# LED_2.net
KiCad netlist of a schematic drawn in Altium Designer
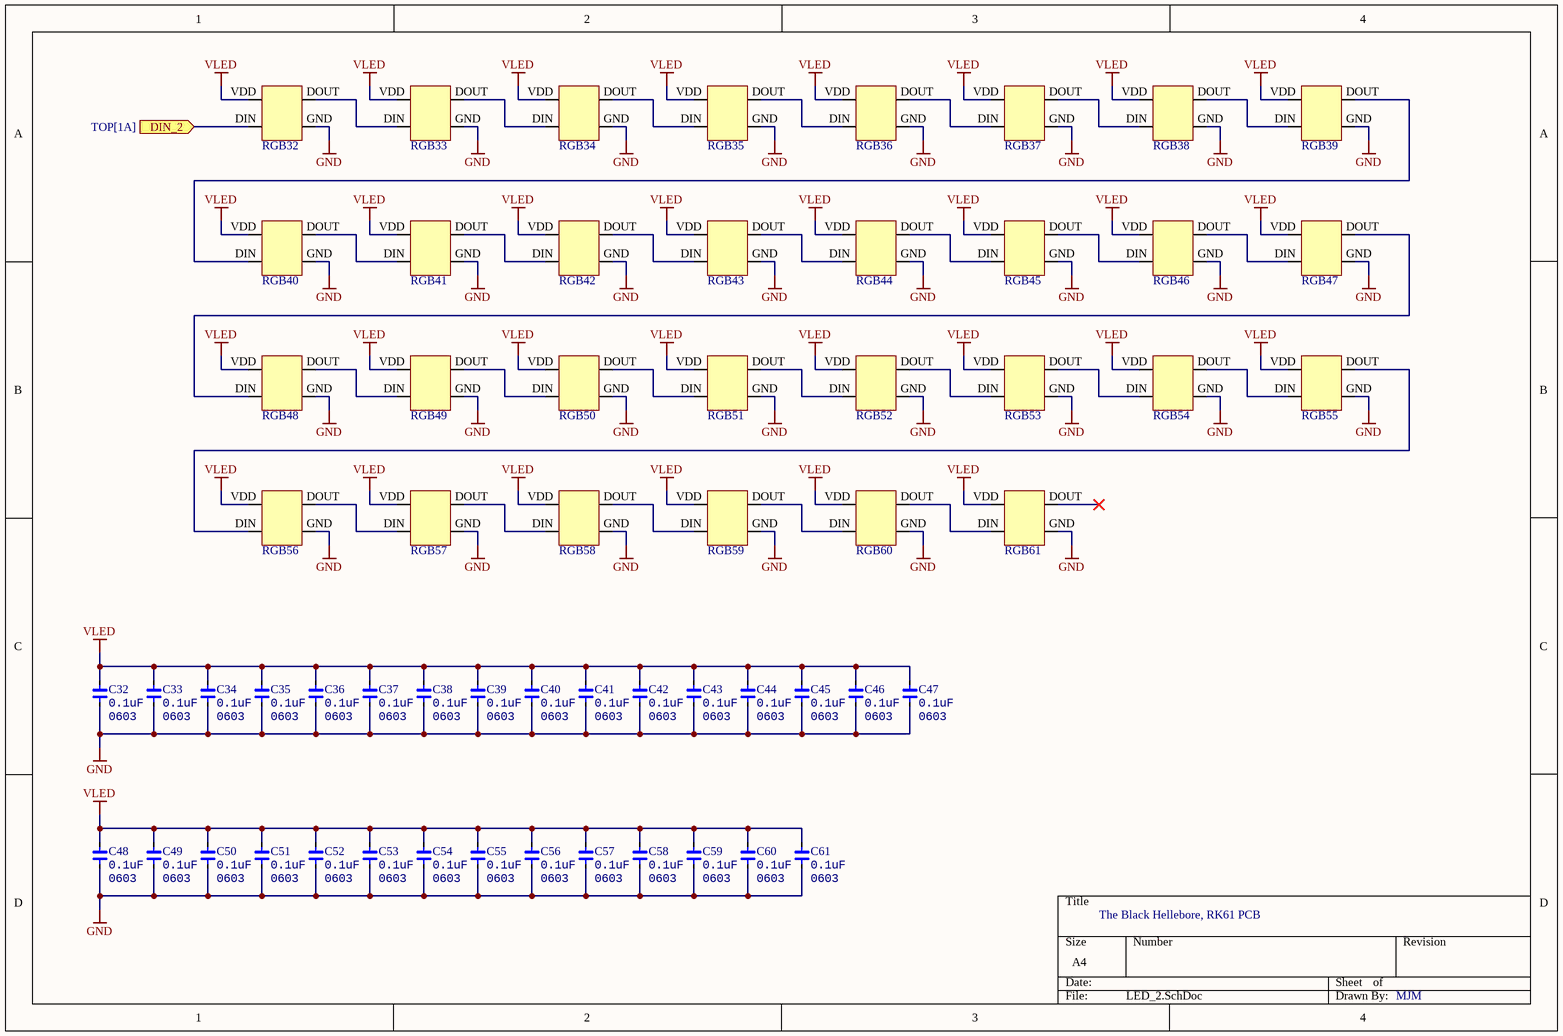
[diagram p0: LED_2.SchDoc]

(export (version "E")
  (design (tool "Eeschema 10.0.6"))
  (components
    (comp (ref "C32")
      (value "0.1uF")
      (footprint "FP-CC0603-DA-MFG")
      (description "0603 0.1 uF 50 V ±5 % Tolerance X7R SMT Multilayer Ceramic Capacitor")
      (fields (field (name "TYPE") "0603") (field (name "Comment") "CC0603JRX7R9BB104"))
      (libsource (lib "Microcom Corporation") (part "M_Cap"))
    )
    (comp (ref "C33")
      (value "0.1uF")
      (footprint "FP-CC0603-DA-MFG")
      (description "0603 0.1 uF 50 V ±5 % Tolerance X7R SMT Multilayer Ceramic Capacitor")
      (fields (field (name "TYPE") "0603") (field (name "Comment") "CC0603JRX7R9BB104"))
      (libsource (lib "Microcom Corporation") (part "M_Cap"))
    )
    (comp (ref "C34")
      (value "0.1uF")
      (footprint "FP-CC0603-DA-MFG")
      (description "0603 0.1 uF 50 V ±5 % Tolerance X7R SMT Multilayer Ceramic Capacitor")
      (fields (field (name "TYPE") "0603") (field (name "Comment") "CC0603JRX7R9BB104"))
      (libsource (lib "Microcom Corporation") (part "M_Cap"))
    )
    (comp (ref "C35")
      (value "0.1uF")
      (footprint "FP-CC0603-DA-MFG")
      (description "0603 0.1 uF 50 V ±5 % Tolerance X7R SMT Multilayer Ceramic Capacitor")
      (fields (field (name "TYPE") "0603") (field (name "Comment") "CC0603JRX7R9BB104"))
      (libsource (lib "Microcom Corporation") (part "M_Cap"))
    )
    (comp (ref "C36")
      (value "0.1uF")
      (footprint "FP-CC0603-DA-MFG")
      (description "0603 0.1 uF 50 V ±5 % Tolerance X7R SMT Multilayer Ceramic Capacitor")
      (fields (field (name "TYPE") "0603") (field (name "Comment") "CC0603JRX7R9BB104"))
      (libsource (lib "Microcom Corporation") (part "M_Cap"))
    )
    (comp (ref "C37")
      (value "0.1uF")
      (footprint "FP-CC0603-DA-MFG")
      (description "0603 0.1 uF 50 V ±5 % Tolerance X7R SMT Multilayer Ceramic Capacitor")
      (fields (field (name "TYPE") "0603") (field (name "Comment") "CC0603JRX7R9BB104"))
      (libsource (lib "Microcom Corporation") (part "M_Cap"))
    )
    (comp (ref "C38")
      (value "0.1uF")
      (footprint "FP-CC0603-DA-MFG")
      (description "0603 0.1 uF 50 V ±5 % Tolerance X7R SMT Multilayer Ceramic Capacitor")
      (fields (field (name "TYPE") "0603") (field (name "Comment") "CC0603JRX7R9BB104"))
      (libsource (lib "Microcom Corporation") (part "M_Cap"))
    )
    (comp (ref "C39")
      (value "0.1uF")
      (footprint "FP-CC0603-DA-MFG")
      (description "0603 0.1 uF 50 V ±5 % Tolerance X7R SMT Multilayer Ceramic Capacitor")
      (fields (field (name "TYPE") "0603") (field (name "Comment") "CC0603JRX7R9BB104"))
      (libsource (lib "Microcom Corporation") (part "M_Cap"))
    )
    (comp (ref "C40")
      (value "0.1uF")
      (footprint "FP-CC0603-DA-MFG")
      (description "0603 0.1 uF 50 V ±5 % Tolerance X7R SMT Multilayer Ceramic Capacitor")
      (fields (field (name "TYPE") "0603") (field (name "Comment") "CC0603JRX7R9BB104"))
      (libsource (lib "Microcom Corporation") (part "M_Cap"))
    )
    (comp (ref "C41")
      (value "0.1uF")
      (footprint "FP-CC0603-DA-MFG")
      (description "0603 0.1 uF 50 V ±5 % Tolerance X7R SMT Multilayer Ceramic Capacitor")
      (fields (field (name "TYPE") "0603") (field (name "Comment") "CC0603JRX7R9BB104"))
      (libsource (lib "Microcom Corporation") (part "M_Cap"))
    )
    (comp (ref "C42")
      (value "0.1uF")
      (footprint "FP-CC0603-DA-MFG")
      (description "0603 0.1 uF 50 V ±5 % Tolerance X7R SMT Multilayer Ceramic Capacitor")
      (fields (field (name "TYPE") "0603") (field (name "Comment") "CC0603JRX7R9BB104"))
      (libsource (lib "Microcom Corporation") (part "M_Cap"))
    )
    (comp (ref "C43")
      (value "0.1uF")
      (footprint "FP-CC0603-DA-MFG")
      (description "0603 0.1 uF 50 V ±5 % Tolerance X7R SMT Multilayer Ceramic Capacitor")
      (fields (field (name "TYPE") "0603") (field (name "Comment") "CC0603JRX7R9BB104"))
      (libsource (lib "Microcom Corporation") (part "M_Cap"))
    )
    (comp (ref "C44")
      (value "0.1uF")
      (footprint "FP-CC0603-DA-MFG")
      (description "0603 0.1 uF 50 V ±5 % Tolerance X7R SMT Multilayer Ceramic Capacitor")
      (fields (field (name "TYPE") "0603") (field (name "Comment") "CC0603JRX7R9BB104"))
      (libsource (lib "Microcom Corporation") (part "M_Cap"))
    )
    (comp (ref "C45")
      (value "0.1uF")
      (footprint "FP-CC0603-DA-MFG")
      (description "0603 0.1 uF 50 V ±5 % Tolerance X7R SMT Multilayer Ceramic Capacitor")
      (fields (field (name "TYPE") "0603") (field (name "Comment") "CC0603JRX7R9BB104"))
      (libsource (lib "Microcom Corporation") (part "M_Cap"))
    )
    (comp (ref "C46")
      (value "0.1uF")
      (footprint "FP-CC0603-DA-MFG")
      (description "0603 0.1 uF 50 V ±5 % Tolerance X7R SMT Multilayer Ceramic Capacitor")
      (fields (field (name "TYPE") "0603") (field (name "Comment") "CC0603JRX7R9BB104"))
      (libsource (lib "Microcom Corporation") (part "M_Cap"))
    )
    (comp (ref "C47")
      (value "0.1uF")
      (footprint "FP-CC0603-DA-MFG")
      (description "0603 0.1 uF 50 V ±5 % Tolerance X7R SMT Multilayer Ceramic Capacitor")
      (fields (field (name "TYPE") "0603") (field (name "Comment") "CC0603JRX7R9BB104"))
      (libsource (lib "Microcom Corporation") (part "M_Cap"))
    )
    (comp (ref "C48")
      (value "0.1uF")
      (footprint "FP-CC0603-DA-MFG")
      (description "0603 0.1 uF 50 V ±5 % Tolerance X7R SMT Multilayer Ceramic Capacitor")
      (fields (field (name "TYPE") "0603") (field (name "Comment") "CC0603JRX7R9BB104"))
      (libsource (lib "Microcom Corporation") (part "M_Cap"))
    )
    (comp (ref "C49")
      (value "0.1uF")
      (footprint "FP-CC0603-DA-MFG")
      (description "0603 0.1 uF 50 V ±5 % Tolerance X7R SMT Multilayer Ceramic Capacitor")
      (fields (field (name "TYPE") "0603") (field (name "Comment") "CC0603JRX7R9BB104"))
      (libsource (lib "Microcom Corporation") (part "M_Cap"))
    )
    (comp (ref "C50")
      (value "0.1uF")
      (footprint "FP-CC0603-DA-MFG")
      (description "0603 0.1 uF 50 V ±5 % Tolerance X7R SMT Multilayer Ceramic Capacitor")
      (fields (field (name "TYPE") "0603") (field (name "Comment") "CC0603JRX7R9BB104"))
      (libsource (lib "Microcom Corporation") (part "M_Cap"))
    )
    (comp (ref "C51")
      (value "0.1uF")
      (footprint "FP-CC0603-DA-MFG")
      (description "0603 0.1 uF 50 V ±5 % Tolerance X7R SMT Multilayer Ceramic Capacitor")
      (fields (field (name "TYPE") "0603") (field (name "Comment") "CC0603JRX7R9BB104"))
      (libsource (lib "Microcom Corporation") (part "M_Cap"))
    )
    (comp (ref "C52")
      (value "0.1uF")
      (footprint "FP-CC0603-DA-MFG")
      (description "0603 0.1 uF 50 V ±5 % Tolerance X7R SMT Multilayer Ceramic Capacitor")
      (fields (field (name "TYPE") "0603") (field (name "Comment") "CC0603JRX7R9BB104"))
      (libsource (lib "Microcom Corporation") (part "M_Cap"))
    )
    (comp (ref "C53")
      (value "0.1uF")
      (footprint "FP-CC0603-DA-MFG")
      (description "0603 0.1 uF 50 V ±5 % Tolerance X7R SMT Multilayer Ceramic Capacitor")
      (fields (field (name "TYPE") "0603") (field (name "Comment") "CC0603JRX7R9BB104"))
      (libsource (lib "Microcom Corporation") (part "M_Cap"))
    )
    (comp (ref "C54")
      (value "0.1uF")
      (footprint "FP-CC0603-DA-MFG")
      (description "0603 0.1 uF 50 V ±5 % Tolerance X7R SMT Multilayer Ceramic Capacitor")
      (fields (field (name "TYPE") "0603") (field (name "Comment") "CC0603JRX7R9BB104"))
      (libsource (lib "Microcom Corporation") (part "M_Cap"))
    )
    (comp (ref "C55")
      (value "0.1uF")
      (footprint "FP-CC0603-DA-MFG")
      (description "0603 0.1 uF 50 V ±5 % Tolerance X7R SMT Multilayer Ceramic Capacitor")
      (fields (field (name "TYPE") "0603") (field (name "Comment") "CC0603JRX7R9BB104"))
      (libsource (lib "Microcom Corporation") (part "M_Cap"))
    )
    (comp (ref "C56")
      (value "0.1uF")
      (footprint "FP-CC0603-DA-MFG")
      (description "0603 0.1 uF 50 V ±5 % Tolerance X7R SMT Multilayer Ceramic Capacitor")
      (fields (field (name "TYPE") "0603") (field (name "Comment") "CC0603JRX7R9BB104"))
      (libsource (lib "Microcom Corporation") (part "M_Cap"))
    )
    (comp (ref "C57")
      (value "0.1uF")
      (footprint "FP-CC0603-DA-MFG")
      (description "0603 0.1 uF 50 V ±5 % Tolerance X7R SMT Multilayer Ceramic Capacitor")
      (fields (field (name "TYPE") "0603") (field (name "Comment") "CC0603JRX7R9BB104"))
      (libsource (lib "Microcom Corporation") (part "M_Cap"))
    )
    (comp (ref "C58")
      (value "0.1uF")
      (footprint "FP-CC0603-DA-MFG")
      (description "0603 0.1 uF 50 V ±5 % Tolerance X7R SMT Multilayer Ceramic Capacitor")
      (fields (field (name "TYPE") "0603") (field (name "Comment") "CC0603JRX7R9BB104"))
      (libsource (lib "Microcom Corporation") (part "M_Cap"))
    )
    (comp (ref "C59")
      (value "0.1uF")
      (footprint "FP-CC0603-DA-MFG")
      (description "0603 0.1 uF 50 V ±5 % Tolerance X7R SMT Multilayer Ceramic Capacitor")
      (fields (field (name "TYPE") "0603") (field (name "Comment") "CC0603JRX7R9BB104"))
      (libsource (lib "Microcom Corporation") (part "M_Cap"))
    )
    (comp (ref "C60")
      (value "0.1uF")
      (footprint "FP-CC0603-DA-MFG")
      (description "0603 0.1 uF 50 V ±5 % Tolerance X7R SMT Multilayer Ceramic Capacitor")
      (fields (field (name "TYPE") "0603") (field (name "Comment") "CC0603JRX7R9BB104"))
      (libsource (lib "Microcom Corporation") (part "M_Cap"))
    )
    (comp (ref "C61")
      (value "0.1uF")
      (footprint "FP-CC0603-DA-MFG")
      (description "0603 0.1 uF 50 V ±5 % Tolerance X7R SMT Multilayer Ceramic Capacitor")
      (fields (field (name "TYPE") "0603") (field (name "Comment") "CC0603JRX7R9BB104"))
      (libsource (lib "Microcom Corporation") (part "M_Cap"))
    )
    (comp (ref "RGB32")
      (value "SK6812MINI-E")
      (footprint "sk6812minie")
      (description "RGB LED SK6812MINI-E")
      (libsource (lib "Microcom Corporation") (part "SK6812MINI-E"))
    )
    (comp (ref "RGB33")
      (value "SK6812MINI-E")
      (footprint "sk6812minie")
      (description "RGB LED SK6812MINI-E")
      (libsource (lib "Microcom Corporation") (part "SK6812MINI-E"))
    )
    (comp (ref "RGB34")
      (value "SK6812MINI-E")
      (footprint "sk6812minie")
      (description "RGB LED SK6812MINI-E")
      (libsource (lib "Microcom Corporation") (part "SK6812MINI-E"))
    )
    (comp (ref "RGB35")
      (value "SK6812MINI-E")
      (footprint "sk6812minie")
      (description "RGB LED SK6812MINI-E")
      (libsource (lib "Microcom Corporation") (part "SK6812MINI-E"))
    )
    (comp (ref "RGB36")
      (value "SK6812MINI-E")
      (footprint "sk6812minie")
      (description "RGB LED SK6812MINI-E")
      (libsource (lib "Microcom Corporation") (part "SK6812MINI-E"))
    )
    (comp (ref "RGB37")
      (value "SK6812MINI-E")
      (footprint "sk6812minie")
      (description "RGB LED SK6812MINI-E")
      (libsource (lib "Microcom Corporation") (part "SK6812MINI-E"))
    )
    (comp (ref "RGB38")
      (value "SK6812MINI-E")
      (footprint "sk6812minie")
      (description "RGB LED SK6812MINI-E")
      (libsource (lib "Microcom Corporation") (part "SK6812MINI-E"))
    )
    (comp (ref "RGB39")
      (value "SK6812MINI-E")
      (footprint "sk6812minie")
      (description "RGB LED SK6812MINI-E")
      (libsource (lib "Microcom Corporation") (part "SK6812MINI-E"))
    )
    (comp (ref "RGB40")
      (value "SK6812MINI-E")
      (footprint "sk6812minie")
      (description "RGB LED SK6812MINI-E")
      (libsource (lib "Microcom Corporation") (part "SK6812MINI-E"))
    )
    (comp (ref "RGB41")
      (value "SK6812MINI-E")
      (footprint "sk6812minie")
      (description "RGB LED SK6812MINI-E")
      (libsource (lib "Microcom Corporation") (part "SK6812MINI-E"))
    )
    (comp (ref "RGB42")
      (value "SK6812MINI-E")
      (footprint "sk6812minie")
      (description "RGB LED SK6812MINI-E")
      (libsource (lib "Microcom Corporation") (part "SK6812MINI-E"))
    )
    (comp (ref "RGB43")
      (value "SK6812MINI-E")
      (footprint "sk6812minie")
      (description "RGB LED SK6812MINI-E")
      (libsource (lib "Microcom Corporation") (part "SK6812MINI-E"))
    )
    (comp (ref "RGB44")
      (value "SK6812MINI-E")
      (footprint "sk6812minie")
      (description "RGB LED SK6812MINI-E")
      (libsource (lib "Microcom Corporation") (part "SK6812MINI-E"))
    )
    (comp (ref "RGB45")
      (value "SK6812MINI-E")
      (footprint "sk6812minie")
      (description "RGB LED SK6812MINI-E")
      (libsource (lib "Microcom Corporation") (part "SK6812MINI-E"))
    )
    (comp (ref "RGB46")
      (value "SK6812MINI-E")
      (footprint "sk6812minie")
      (description "RGB LED SK6812MINI-E")
      (libsource (lib "Microcom Corporation") (part "SK6812MINI-E"))
    )
    (comp (ref "RGB47")
      (value "SK6812MINI-E")
      (footprint "sk6812minie")
      (description "RGB LED SK6812MINI-E")
      (libsource (lib "Microcom Corporation") (part "SK6812MINI-E"))
    )
    (comp (ref "RGB48")
      (value "SK6812MINI-E")
      (footprint "sk6812minie")
      (description "RGB LED SK6812MINI-E")
      (libsource (lib "Microcom Corporation") (part "SK6812MINI-E"))
    )
    (comp (ref "RGB49")
      (value "SK6812MINI-E")
      (footprint "sk6812minie")
      (description "RGB LED SK6812MINI-E")
      (libsource (lib "Microcom Corporation") (part "SK6812MINI-E"))
    )
    (comp (ref "RGB50")
      (value "SK6812MINI-E")
      (footprint "sk6812minie")
      (description "RGB LED SK6812MINI-E")
      (libsource (lib "Microcom Corporation") (part "SK6812MINI-E"))
    )
    (comp (ref "RGB51")
      (value "SK6812MINI-E")
      (footprint "sk6812minie")
      (description "RGB LED SK6812MINI-E")
      (libsource (lib "Microcom Corporation") (part "SK6812MINI-E"))
    )
    (comp (ref "RGB52")
      (value "SK6812MINI-E")
      (footprint "sk6812minie")
      (description "RGB LED SK6812MINI-E")
      (libsource (lib "Microcom Corporation") (part "SK6812MINI-E"))
    )
    (comp (ref "RGB53")
      (value "SK6812MINI-E")
      (footprint "sk6812minie")
      (description "RGB LED SK6812MINI-E")
      (libsource (lib "Microcom Corporation") (part "SK6812MINI-E"))
    )
    (comp (ref "RGB54")
      (value "SK6812MINI-E")
      (footprint "sk6812minie")
      (description "RGB LED SK6812MINI-E")
      (libsource (lib "Microcom Corporation") (part "SK6812MINI-E"))
    )
    (comp (ref "RGB55")
      (value "SK6812MINI-E")
      (footprint "sk6812minie")
      (description "RGB LED SK6812MINI-E")
      (libsource (lib "Microcom Corporation") (part "SK6812MINI-E"))
    )
    (comp (ref "RGB56")
      (value "SK6812MINI-E")
      (footprint "sk6812minie")
      (description "RGB LED SK6812MINI-E")
      (libsource (lib "Microcom Corporation") (part "SK6812MINI-E"))
    )
    (comp (ref "RGB57")
      (value "SK6812MINI-E")
      (footprint "sk6812minie")
      (description "RGB LED SK6812MINI-E")
      (libsource (lib "Microcom Corporation") (part "SK6812MINI-E"))
    )
    (comp (ref "RGB58")
      (value "SK6812MINI-E")
      (footprint "sk6812minie")
      (description "RGB LED SK6812MINI-E")
      (libsource (lib "Microcom Corporation") (part "SK6812MINI-E"))
    )
    (comp (ref "RGB59")
      (value "SK6812MINI-E")
      (footprint "sk6812minie")
      (description "RGB LED SK6812MINI-E")
      (libsource (lib "Microcom Corporation") (part "SK6812MINI-E"))
    )
    (comp (ref "RGB60")
      (value "SK6812MINI-E")
      (footprint "sk6812minie")
      (description "RGB LED SK6812MINI-E")
      (libsource (lib "Microcom Corporation") (part "SK6812MINI-E"))
    )
    (comp (ref "RGB61")
      (value "SK6812MINI-E")
      (footprint "sk6812minie")
      (description "RGB LED SK6812MINI-E")
      (libsource (lib "Microcom Corporation") (part "SK6812MINI-E"))
    )
  )
  (nets
    (net (code "1") (name "/DIN_2") (class "Default")
      (node (ref "RGB32") (pin "DIN") (pinfunction "DIN_DIN") (pintype "passive"))
    )
    (net (code "2") (name "GND") (class "Default")
      (node (ref "C32") (pin "1") (pinfunction "1_1") (pintype "passive"))
      (node (ref "C33") (pin "1") (pinfunction "1_1") (pintype "passive"))
      (node (ref "C34") (pin "1") (pinfunction "1_1") (pintype "passive"))
      (node (ref "C35") (pin "1") (pinfunction "1_1") (pintype "passive"))
      (node (ref "C36") (pin "1") (pinfunction "1_1") (pintype "passive"))
      (node (ref "C37") (pin "1") (pinfunction "1_1") (pintype "passive"))
      (node (ref "C38") (pin "1") (pinfunction "1_1") (pintype "passive"))
      (node (ref "C39") (pin "1") (pinfunction "1_1") (pintype "passive"))
      (node (ref "C40") (pin "1") (pinfunction "1_1") (pintype "passive"))
      (node (ref "C41") (pin "1") (pinfunction "1_1") (pintype "passive"))
      (node (ref "C42") (pin "1") (pinfunction "1_1") (pintype "passive"))
      (node (ref "C43") (pin "1") (pinfunction "1_1") (pintype "passive"))
      (node (ref "C44") (pin "1") (pinfunction "1_1") (pintype "passive"))
      (node (ref "C45") (pin "1") (pinfunction "1_1") (pintype "passive"))
      (node (ref "C46") (pin "1") (pinfunction "1_1") (pintype "passive"))
      (node (ref "C47") (pin "1") (pinfunction "1_1") (pintype "passive"))
      (node (ref "C48") (pin "1") (pinfunction "1_1") (pintype "passive"))
      (node (ref "C49") (pin "1") (pinfunction "1_1") (pintype "passive"))
      (node (ref "C50") (pin "1") (pinfunction "1_1") (pintype "passive"))
      (node (ref "C51") (pin "1") (pinfunction "1_1") (pintype "passive"))
      (node (ref "C52") (pin "1") (pinfunction "1_1") (pintype "passive"))
      (node (ref "C53") (pin "1") (pinfunction "1_1") (pintype "passive"))
      (node (ref "C54") (pin "1") (pinfunction "1_1") (pintype "passive"))
      (node (ref "C55") (pin "1") (pinfunction "1_1") (pintype "passive"))
      (node (ref "C56") (pin "1") (pinfunction "1_1") (pintype "passive"))
      (node (ref "C57") (pin "1") (pinfunction "1_1") (pintype "passive"))
      (node (ref "C58") (pin "1") (pinfunction "1_1") (pintype "passive"))
      (node (ref "C59") (pin "1") (pinfunction "1_1") (pintype "passive"))
      (node (ref "C60") (pin "1") (pinfunction "1_1") (pintype "passive"))
      (node (ref "C61") (pin "1") (pinfunction "1_1") (pintype "passive"))
      (node (ref "RGB32") (pin "GND") (pinfunction "GND_GND") (pintype "passive"))
      (node (ref "RGB33") (pin "GND") (pinfunction "GND_GND") (pintype "passive"))
      (node (ref "RGB34") (pin "GND") (pinfunction "GND_GND") (pintype "passive"))
      (node (ref "RGB35") (pin "GND") (pinfunction "GND_GND") (pintype "passive"))
      (node (ref "RGB36") (pin "GND") (pinfunction "GND_GND") (pintype "passive"))
      (node (ref "RGB37") (pin "GND") (pinfunction "GND_GND") (pintype "passive"))
      (node (ref "RGB38") (pin "GND") (pinfunction "GND_GND") (pintype "passive"))
      (node (ref "RGB39") (pin "GND") (pinfunction "GND_GND") (pintype "passive"))
      (node (ref "RGB40") (pin "GND") (pinfunction "GND_GND") (pintype "passive"))
      (node (ref "RGB41") (pin "GND") (pinfunction "GND_GND") (pintype "passive"))
      (node (ref "RGB42") (pin "GND") (pinfunction "GND_GND") (pintype "passive"))
      (node (ref "RGB43") (pin "GND") (pinfunction "GND_GND") (pintype "passive"))
      (node (ref "RGB44") (pin "GND") (pinfunction "GND_GND") (pintype "passive"))
      (node (ref "RGB45") (pin "GND") (pinfunction "GND_GND") (pintype "passive"))
      (node (ref "RGB46") (pin "GND") (pinfunction "GND_GND") (pintype "passive"))
      (node (ref "RGB47") (pin "GND") (pinfunction "GND_GND") (pintype "passive"))
      (node (ref "RGB48") (pin "GND") (pinfunction "GND_GND") (pintype "passive"))
      (node (ref "RGB49") (pin "GND") (pinfunction "GND_GND") (pintype "passive"))
      (node (ref "RGB50") (pin "GND") (pinfunction "GND_GND") (pintype "passive"))
      (node (ref "RGB51") (pin "GND") (pinfunction "GND_GND") (pintype "passive"))
      (node (ref "RGB52") (pin "GND") (pinfunction "GND_GND") (pintype "passive"))
      (node (ref "RGB53") (pin "GND") (pinfunction "GND_GND") (pintype "passive"))
      (node (ref "RGB54") (pin "GND") (pinfunction "GND_GND") (pintype "passive"))
      (node (ref "RGB55") (pin "GND") (pinfunction "GND_GND") (pintype "passive"))
      (node (ref "RGB56") (pin "GND") (pinfunction "GND_GND") (pintype "passive"))
      (node (ref "RGB57") (pin "GND") (pinfunction "GND_GND") (pintype "passive"))
      (node (ref "RGB58") (pin "GND") (pinfunction "GND_GND") (pintype "passive"))
      (node (ref "RGB59") (pin "GND") (pinfunction "GND_GND") (pintype "passive"))
      (node (ref "RGB60") (pin "GND") (pinfunction "GND_GND") (pintype "passive"))
      (node (ref "RGB61") (pin "GND") (pinfunction "GND_GND") (pintype "passive"))
    )
    (net (code "3") (name "Net-(RGB32-PadDOUT)") (class "Default")
      (node (ref "RGB32") (pin "DOUT") (pinfunction "DOUT_DOUT") (pintype "passive"))
      (node (ref "RGB33") (pin "DIN") (pinfunction "DIN_DIN") (pintype "passive"))
    )
    (net (code "4") (name "Net-(RGB33-PadDOUT)") (class "Default")
      (node (ref "RGB33") (pin "DOUT") (pinfunction "DOUT_DOUT") (pintype "passive"))
      (node (ref "RGB34") (pin "DIN") (pinfunction "DIN_DIN") (pintype "passive"))
    )
    (net (code "5") (name "Net-(RGB34-PadDOUT)") (class "Default")
      (node (ref "RGB34") (pin "DOUT") (pinfunction "DOUT_DOUT") (pintype "passive"))
      (node (ref "RGB35") (pin "DIN") (pinfunction "DIN_DIN") (pintype "passive"))
    )
    (net (code "6") (name "Net-(RGB35-PadDOUT)") (class "Default")
      (node (ref "RGB35") (pin "DOUT") (pinfunction "DOUT_DOUT") (pintype "passive"))
      (node (ref "RGB36") (pin "DIN") (pinfunction "DIN_DIN") (pintype "passive"))
    )
    (net (code "7") (name "Net-(RGB36-PadDOUT)") (class "Default")
      (node (ref "RGB36") (pin "DOUT") (pinfunction "DOUT_DOUT") (pintype "passive"))
      (node (ref "RGB37") (pin "DIN") (pinfunction "DIN_DIN") (pintype "passive"))
    )
    (net (code "8") (name "Net-(RGB37-PadDOUT)") (class "Default")
      (node (ref "RGB37") (pin "DOUT") (pinfunction "DOUT_DOUT") (pintype "passive"))
      (node (ref "RGB38") (pin "DIN") (pinfunction "DIN_DIN") (pintype "passive"))
    )
    (net (code "9") (name "Net-(RGB38-PadDOUT)") (class "Default")
      (node (ref "RGB38") (pin "DOUT") (pinfunction "DOUT_DOUT") (pintype "passive"))
      (node (ref "RGB39") (pin "DIN") (pinfunction "DIN_DIN") (pintype "passive"))
    )
    (net (code "10") (name "Net-(RGB39-PadDOUT)") (class "Default")
      (node (ref "RGB39") (pin "DOUT") (pinfunction "DOUT_DOUT") (pintype "passive"))
      (node (ref "RGB40") (pin "DIN") (pinfunction "DIN_DIN") (pintype "passive"))
    )
    (net (code "11") (name "Net-(RGB40-PadDOUT)") (class "Default")
      (node (ref "RGB40") (pin "DOUT") (pinfunction "DOUT_DOUT") (pintype "passive"))
      (node (ref "RGB41") (pin "DIN") (pinfunction "DIN_DIN") (pintype "passive"))
    )
    (net (code "12") (name "Net-(RGB41-PadDOUT)") (class "Default")
      (node (ref "RGB41") (pin "DOUT") (pinfunction "DOUT_DOUT") (pintype "passive"))
      (node (ref "RGB42") (pin "DIN") (pinfunction "DIN_DIN") (pintype "passive"))
    )
    (net (code "13") (name "Net-(RGB42-PadDOUT)") (class "Default")
      (node (ref "RGB42") (pin "DOUT") (pinfunction "DOUT_DOUT") (pintype "passive"))
      (node (ref "RGB43") (pin "DIN") (pinfunction "DIN_DIN") (pintype "passive"))
    )
    (net (code "14") (name "Net-(RGB43-PadDOUT)") (class "Default")
      (node (ref "RGB43") (pin "DOUT") (pinfunction "DOUT_DOUT") (pintype "passive"))
      (node (ref "RGB44") (pin "DIN") (pinfunction "DIN_DIN") (pintype "passive"))
    )
    (net (code "15") (name "Net-(RGB44-PadDOUT)") (class "Default")
      (node (ref "RGB44") (pin "DOUT") (pinfunction "DOUT_DOUT") (pintype "passive"))
      (node (ref "RGB45") (pin "DIN") (pinfunction "DIN_DIN") (pintype "passive"))
    )
    (net (code "16") (name "Net-(RGB45-PadDOUT)") (class "Default")
      (node (ref "RGB45") (pin "DOUT") (pinfunction "DOUT_DOUT") (pintype "passive"))
      (node (ref "RGB46") (pin "DIN") (pinfunction "DIN_DIN") (pintype "passive"))
    )
    (net (code "17") (name "Net-(RGB46-PadDOUT)") (class "Default")
      (node (ref "RGB46") (pin "DOUT") (pinfunction "DOUT_DOUT") (pintype "passive"))
      (node (ref "RGB47") (pin "DIN") (pinfunction "DIN_DIN") (pintype "passive"))
    )
    (net (code "18") (name "Net-(RGB47-PadDOUT)") (class "Default")
      (node (ref "RGB47") (pin "DOUT") (pinfunction "DOUT_DOUT") (pintype "passive"))
      (node (ref "RGB48") (pin "DIN") (pinfunction "DIN_DIN") (pintype "passive"))
    )
    (net (code "19") (name "Net-(RGB48-PadDOUT)") (class "Default")
      (node (ref "RGB48") (pin "DOUT") (pinfunction "DOUT_DOUT") (pintype "passive"))
      (node (ref "RGB49") (pin "DIN") (pinfunction "DIN_DIN") (pintype "passive"))
    )
    (net (code "20") (name "Net-(RGB49-PadDOUT)") (class "Default")
      (node (ref "RGB49") (pin "DOUT") (pinfunction "DOUT_DOUT") (pintype "passive"))
      (node (ref "RGB50") (pin "DIN") (pinfunction "DIN_DIN") (pintype "passive"))
    )
    (net (code "21") (name "Net-(RGB50-PadDOUT)") (class "Default")
      (node (ref "RGB50") (pin "DOUT") (pinfunction "DOUT_DOUT") (pintype "passive"))
      (node (ref "RGB51") (pin "DIN") (pinfunction "DIN_DIN") (pintype "passive"))
    )
    (net (code "22") (name "Net-(RGB51-PadDOUT)") (class "Default")
      (node (ref "RGB51") (pin "DOUT") (pinfunction "DOUT_DOUT") (pintype "passive"))
      (node (ref "RGB52") (pin "DIN") (pinfunction "DIN_DIN") (pintype "passive"))
    )
    (net (code "23") (name "Net-(RGB52-PadDOUT)") (class "Default")
      (node (ref "RGB52") (pin "DOUT") (pinfunction "DOUT_DOUT") (pintype "passive"))
      (node (ref "RGB53") (pin "DIN") (pinfunction "DIN_DIN") (pintype "passive"))
    )
    (net (code "24") (name "Net-(RGB53-PadDOUT)") (class "Default")
      (node (ref "RGB53") (pin "DOUT") (pinfunction "DOUT_DOUT") (pintype "passive"))
      (node (ref "RGB54") (pin "DIN") (pinfunction "DIN_DIN") (pintype "passive"))
    )
    (net (code "25") (name "Net-(RGB54-PadDOUT)") (class "Default")
      (node (ref "RGB54") (pin "DOUT") (pinfunction "DOUT_DOUT") (pintype "passive"))
      (node (ref "RGB55") (pin "DIN") (pinfunction "DIN_DIN") (pintype "passive"))
    )
    (net (code "26") (name "Net-(RGB55-PadDOUT)") (class "Default")
      (node (ref "RGB55") (pin "DOUT") (pinfunction "DOUT_DOUT") (pintype "passive"))
      (node (ref "RGB56") (pin "DIN") (pinfunction "DIN_DIN") (pintype "passive"))
    )
    (net (code "27") (name "Net-(RGB56-PadDOUT)") (class "Default")
      (node (ref "RGB56") (pin "DOUT") (pinfunction "DOUT_DOUT") (pintype "passive"))
      (node (ref "RGB57") (pin "DIN") (pinfunction "DIN_DIN") (pintype "passive"))
    )
    (net (code "28") (name "Net-(RGB57-PadDOUT)") (class "Default")
      (node (ref "RGB57") (pin "DOUT") (pinfunction "DOUT_DOUT") (pintype "passive"))
      (node (ref "RGB58") (pin "DIN") (pinfunction "DIN_DIN") (pintype "passive"))
    )
    (net (code "29") (name "Net-(RGB58-PadDOUT)") (class "Default")
      (node (ref "RGB58") (pin "DOUT") (pinfunction "DOUT_DOUT") (pintype "passive"))
      (node (ref "RGB59") (pin "DIN") (pinfunction "DIN_DIN") (pintype "passive"))
    )
    (net (code "30") (name "Net-(RGB59-PadDOUT)") (class "Default")
      (node (ref "RGB59") (pin "DOUT") (pinfunction "DOUT_DOUT") (pintype "passive"))
      (node (ref "RGB60") (pin "DIN") (pinfunction "DIN_DIN") (pintype "passive"))
    )
    (net (code "31") (name "Net-(RGB60-PadDOUT)") (class "Default")
      (node (ref "RGB60") (pin "DOUT") (pinfunction "DOUT_DOUT") (pintype "passive"))
      (node (ref "RGB61") (pin "DIN") (pinfunction "DIN_DIN") (pintype "passive"))
    )
    (net (code "32") (name "VLED") (class "Default")
      (node (ref "C32") (pin "2") (pinfunction "2_2") (pintype "passive"))
      (node (ref "C33") (pin "2") (pinfunction "2_2") (pintype "passive"))
      (node (ref "C34") (pin "2") (pinfunction "2_2") (pintype "passive"))
      (node (ref "C35") (pin "2") (pinfunction "2_2") (pintype "passive"))
      (node (ref "C36") (pin "2") (pinfunction "2_2") (pintype "passive"))
      (node (ref "C37") (pin "2") (pinfunction "2_2") (pintype "passive"))
      (node (ref "C38") (pin "2") (pinfunction "2_2") (pintype "passive"))
      (node (ref "C39") (pin "2") (pinfunction "2_2") (pintype "passive"))
      (node (ref "C40") (pin "2") (pinfunction "2_2") (pintype "passive"))
      (node (ref "C41") (pin "2") (pinfunction "2_2") (pintype "passive"))
      (node (ref "C42") (pin "2") (pinfunction "2_2") (pintype "passive"))
      (node (ref "C43") (pin "2") (pinfunction "2_2") (pintype "passive"))
      (node (ref "C44") (pin "2") (pinfunction "2_2") (pintype "passive"))
      (node (ref "C45") (pin "2") (pinfunction "2_2") (pintype "passive"))
      (node (ref "C46") (pin "2") (pinfunction "2_2") (pintype "passive"))
      (node (ref "C47") (pin "2") (pinfunction "2_2") (pintype "passive"))
      (node (ref "C48") (pin "2") (pinfunction "2_2") (pintype "passive"))
      (node (ref "C49") (pin "2") (pinfunction "2_2") (pintype "passive"))
      (node (ref "C50") (pin "2") (pinfunction "2_2") (pintype "passive"))
      (node (ref "C51") (pin "2") (pinfunction "2_2") (pintype "passive"))
      (node (ref "C52") (pin "2") (pinfunction "2_2") (pintype "passive"))
      (node (ref "C53") (pin "2") (pinfunction "2_2") (pintype "passive"))
      (node (ref "C54") (pin "2") (pinfunction "2_2") (pintype "passive"))
      (node (ref "C55") (pin "2") (pinfunction "2_2") (pintype "passive"))
      (node (ref "C56") (pin "2") (pinfunction "2_2") (pintype "passive"))
      (node (ref "C57") (pin "2") (pinfunction "2_2") (pintype "passive"))
      (node (ref "C58") (pin "2") (pinfunction "2_2") (pintype "passive"))
      (node (ref "C59") (pin "2") (pinfunction "2_2") (pintype "passive"))
      (node (ref "C60") (pin "2") (pinfunction "2_2") (pintype "passive"))
      (node (ref "C61") (pin "2") (pinfunction "2_2") (pintype "passive"))
      (node (ref "RGB32") (pin "VDD") (pinfunction "VDD_VDD") (pintype "passive"))
      (node (ref "RGB33") (pin "VDD") (pinfunction "VDD_VDD") (pintype "passive"))
      (node (ref "RGB34") (pin "VDD") (pinfunction "VDD_VDD") (pintype "passive"))
      (node (ref "RGB35") (pin "VDD") (pinfunction "VDD_VDD") (pintype "passive"))
      (node (ref "RGB36") (pin "VDD") (pinfunction "VDD_VDD") (pintype "passive"))
      (node (ref "RGB37") (pin "VDD") (pinfunction "VDD_VDD") (pintype "passive"))
      (node (ref "RGB38") (pin "VDD") (pinfunction "VDD_VDD") (pintype "passive"))
      (node (ref "RGB39") (pin "VDD") (pinfunction "VDD_VDD") (pintype "passive"))
      (node (ref "RGB40") (pin "VDD") (pinfunction "VDD_VDD") (pintype "passive"))
      (node (ref "RGB41") (pin "VDD") (pinfunction "VDD_VDD") (pintype "passive"))
      (node (ref "RGB42") (pin "VDD") (pinfunction "VDD_VDD") (pintype "passive"))
      (node (ref "RGB43") (pin "VDD") (pinfunction "VDD_VDD") (pintype "passive"))
      (node (ref "RGB44") (pin "VDD") (pinfunction "VDD_VDD") (pintype "passive"))
      (node (ref "RGB45") (pin "VDD") (pinfunction "VDD_VDD") (pintype "passive"))
      (node (ref "RGB46") (pin "VDD") (pinfunction "VDD_VDD") (pintype "passive"))
      (node (ref "RGB47") (pin "VDD") (pinfunction "VDD_VDD") (pintype "passive"))
      (node (ref "RGB48") (pin "VDD") (pinfunction "VDD_VDD") (pintype "passive"))
      (node (ref "RGB49") (pin "VDD") (pinfunction "VDD_VDD") (pintype "passive"))
      (node (ref "RGB50") (pin "VDD") (pinfunction "VDD_VDD") (pintype "passive"))
      (node (ref "RGB51") (pin "VDD") (pinfunction "VDD_VDD") (pintype "passive"))
      (node (ref "RGB52") (pin "VDD") (pinfunction "VDD_VDD") (pintype "passive"))
      (node (ref "RGB53") (pin "VDD") (pinfunction "VDD_VDD") (pintype "passive"))
      (node (ref "RGB54") (pin "VDD") (pinfunction "VDD_VDD") (pintype "passive"))
      (node (ref "RGB55") (pin "VDD") (pinfunction "VDD_VDD") (pintype "passive"))
      (node (ref "RGB56") (pin "VDD") (pinfunction "VDD_VDD") (pintype "passive"))
      (node (ref "RGB57") (pin "VDD") (pinfunction "VDD_VDD") (pintype "passive"))
      (node (ref "RGB58") (pin "VDD") (pinfunction "VDD_VDD") (pintype "passive"))
      (node (ref "RGB59") (pin "VDD") (pinfunction "VDD_VDD") (pintype "passive"))
      (node (ref "RGB60") (pin "VDD") (pinfunction "VDD_VDD") (pintype "passive"))
      (node (ref "RGB61") (pin "VDD") (pinfunction "VDD_VDD") (pintype "passive"))
    )
    (net (code "33") (name "unconnected-(RGB61-PadDOUT)") (class "Default")
      (node (ref "RGB61") (pin "DOUT") (pinfunction "DOUT_DOUT") (pintype "passive+no_connect"))
    )
  )
)
